# rotaryboard-small.net
KiCad netlist of a schematic drawn in EAGLE
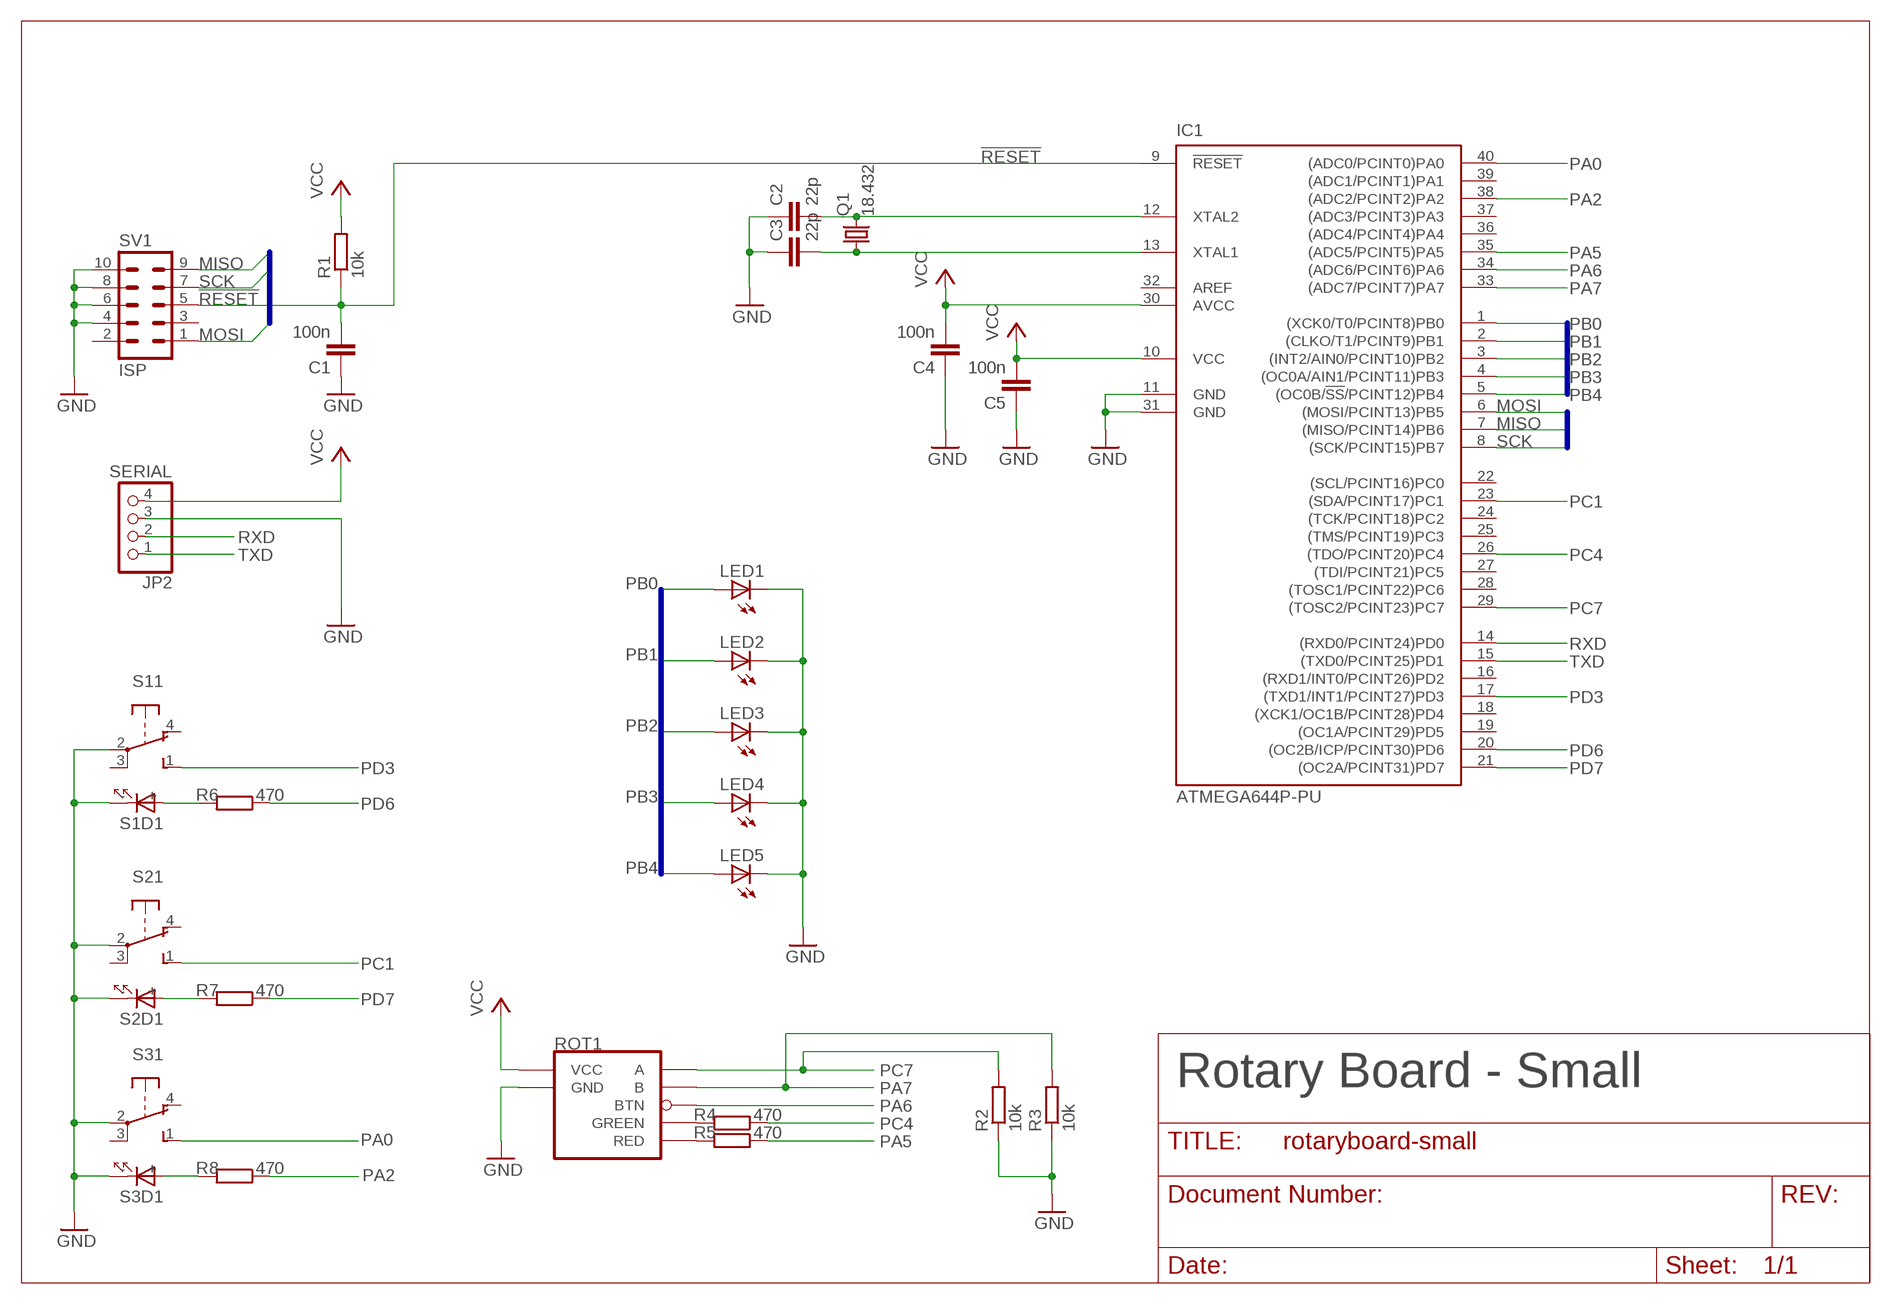
[diagram p0: schematic, sheet 1]

(export (version "E")
  (design (tool "Eeschema 10.0.6"))
  (components
    (comp (ref "C1")
      (value "100n")
      (footprint "eagle-import:C050-025X075")
      (libsource (lib "eagle-import") (part "C-EU050-025X075"))
    )
    (comp (ref "C2")
      (value "22p")
      (footprint "eagle-import:C050-025X075")
      (libsource (lib "eagle-import") (part "C-EU050-025X075"))
    )
    (comp (ref "C3")
      (value "22p")
      (footprint "eagle-import:C050-025X075")
      (libsource (lib "eagle-import") (part "C-EU050-025X075"))
    )
    (comp (ref "C4")
      (value "100n")
      (footprint "eagle-import:C050-025X075")
      (libsource (lib "eagle-import") (part "C-EU050-025X075"))
    )
    (comp (ref "C5")
      (value "100n")
      (footprint "eagle-import:C050-025X075")
      (libsource (lib "eagle-import") (part "C-EU050-025X075"))
    )
    (comp (ref "IC1")
      (value "ATMEGA644P-PU")
      (footprint "eagle-import:DIL40")
      (libsource (lib "eagle-import") (part "MEGA164P/324P/644P-PU"))
    )
    (comp (ref "JP2")
      (value "SERIAL")
      (footprint "eagle-import:1X04")
      (libsource (lib "eagle-import") (part "PINHD-1X4"))
    )
    (comp (ref "LED1")
      (value "LED3MM")
      (footprint "eagle-import:LED3MM")
      (libsource (lib "eagle-import") (part "LED3MM"))
    )
    (comp (ref "LED2")
      (value "LED3MM")
      (footprint "eagle-import:LED3MM")
      (libsource (lib "eagle-import") (part "LED3MM"))
    )
    (comp (ref "LED3")
      (value "LED3MM")
      (footprint "eagle-import:LED3MM")
      (libsource (lib "eagle-import") (part "LED3MM"))
    )
    (comp (ref "LED4")
      (value "LED3MM")
      (footprint "eagle-import:LED3MM")
      (libsource (lib "eagle-import") (part "LED3MM"))
    )
    (comp (ref "LED5")
      (value "LED3MM")
      (footprint "eagle-import:LED3MM")
      (libsource (lib "eagle-import") (part "LED3MM"))
    )
    (comp (ref "Q1")
      (value "18.432")
      (footprint "eagle-import:HC18U-V")
      (libsource (lib "eagle-import") (part "CRYSTALHC18U-V"))
    )
    (comp (ref "R1")
      (value "10k")
      (footprint "eagle-import:0207_10")
      (libsource (lib "eagle-import") (part "R-EU_0207/10"))
    )
    (comp (ref "R2")
      (value "10k")
      (footprint "eagle-import:0207_10")
      (libsource (lib "eagle-import") (part "R-EU_0207/10"))
    )
    (comp (ref "R3")
      (value "10k")
      (footprint "eagle-import:0207_10")
      (libsource (lib "eagle-import") (part "R-EU_0207/10"))
    )
    (comp (ref "R4")
      (value "470")
      (footprint "eagle-import:0207_10")
      (libsource (lib "eagle-import") (part "R-EU_0207/10"))
    )
    (comp (ref "R5")
      (value "470")
      (footprint "eagle-import:0207_10")
      (libsource (lib "eagle-import") (part "R-EU_0207/10"))
    )
    (comp (ref "R6")
      (value "470")
      (footprint "eagle-import:0207_10")
      (libsource (lib "eagle-import") (part "R-EU_0207/10"))
    )
    (comp (ref "R7")
      (value "470")
      (footprint "eagle-import:0207_10")
      (libsource (lib "eagle-import") (part "R-EU_0207/10"))
    )
    (comp (ref "R8")
      (value "470")
      (footprint "eagle-import:0207_10")
      (libsource (lib "eagle-import") (part "R-EU_0207/10"))
    )
    (comp (ref "ROT1")
      (value "DPL12SVCUSTOM")
      (footprint "eagle-import:DPL12SV")
      (libsource (lib "eagle-import") (part "DPL12SVCUSTOM"))
    )
    (comp (ref "S1")
      (value "SRKL")
      (footprint "eagle-import:SRKL")
      (libsource (lib "eagle-import") (part "SRKL"))
    )
    (comp (ref "S2")
      (value "SRKL")
      (footprint "eagle-import:SRKL")
      (libsource (lib "eagle-import") (part "SRKL"))
    )
    (comp (ref "S3")
      (value "SRKL")
      (footprint "eagle-import:SRKL")
      (libsource (lib "eagle-import") (part "SRKL"))
    )
    (comp (ref "SV1")
      (value "ISP")
      (footprint "eagle-import:ML10")
      (libsource (lib "eagle-import") (part "ML10"))
    )
  )
  (nets
    (net (code "6") (name "/AREF") (class "Default")
      (node (ref "IC1") (pin "32") (pinfunction "AREF_32") (pintype "power_in"))
    )
    (net (code "7") (name "/LEDS:PB[0..4]") (class "Default")
      (node (ref "IC1") (pin "5") (pinfunction "(OC0B/~{SS}/PCINT12)PB4_5") (pintype "bidirectional"))
      (node (ref "LED5") (pin "A") (pinfunction "A_A") (pintype "passive"))
    )
    (net (code "8") (name "/MISO") (class "Default")
      (node (ref "IC1") (pin "7") (pinfunction "(MISO/PCINT14)PB6_7") (pintype "bidirectional"))
      (node (ref "SV1") (pin "9") (pinfunction "9_9") (pintype "passive"))
    )
    (net (code "9") (name "/MOSI") (class "Default")
      (node (ref "IC1") (pin "6") (pinfunction "(MOSI/PCINT13)PB5_6") (pintype "bidirectional"))
      (node (ref "SV1") (pin "1") (pinfunction "1_1") (pintype "passive"))
    )
    (net (code "10") (name "/PA0") (class "Default")
      (node (ref "IC1") (pin "40") (pinfunction "(ADC0/PCINT0)PA0_40") (pintype "bidirectional"))
      (node (ref "S3") (pin "1") (pinfunction "S_1") (pintype "passive"))
    )
    (net (code "11") (name "/PA2") (class "Default")
      (node (ref "IC1") (pin "38") (pinfunction "(ADC2/PCINT2)PA2_38") (pintype "bidirectional"))
      (node (ref "R8") (pin "1") (pinfunction "1_1") (pintype "passive"))
    )
    (net (code "12") (name "/PA5") (class "Default")
      (node (ref "IC1") (pin "35") (pinfunction "(ADC5/PCINT5)PA5_35") (pintype "bidirectional"))
      (node (ref "R5") (pin "1") (pinfunction "1_1") (pintype "passive"))
    )
    (net (code "13") (name "/PA6") (class "Default")
      (node (ref "IC1") (pin "34") (pinfunction "(ADC6/PCINT6)PA6_34") (pintype "bidirectional"))
      (node (ref "ROT1") (pin "BTN") (pinfunction "BTN_BTN") (pintype "output"))
    )
    (net (code "14") (name "/PA7") (class "Default")
      (node (ref "IC1") (pin "33") (pinfunction "(ADC7/PCINT7)PA7_33") (pintype "bidirectional"))
      (node (ref "R3") (pin "2") (pinfunction "2_2") (pintype "passive"))
      (node (ref "ROT1") (pin "B") (pinfunction "B_B") (pintype "output"))
    )
    (net (code "15") (name "/PB0") (class "Default")
      (node (ref "IC1") (pin "1") (pinfunction "(XCK0/T0/PCINT8)PB0_1") (pintype "bidirectional"))
      (node (ref "LED1") (pin "A") (pinfunction "A_A") (pintype "passive"))
    )
    (net (code "16") (name "/PB1") (class "Default")
      (node (ref "IC1") (pin "2") (pinfunction "(CLKO/T1/PCINT9)PB1_2") (pintype "bidirectional"))
      (node (ref "LED2") (pin "A") (pinfunction "A_A") (pintype "passive"))
    )
    (net (code "17") (name "/PB2") (class "Default")
      (node (ref "IC1") (pin "3") (pinfunction "(INT2/AIN0/PCINT10)PB2_3") (pintype "bidirectional"))
      (node (ref "LED3") (pin "A") (pinfunction "A_A") (pintype "passive"))
    )
    (net (code "18") (name "/PB3") (class "Default")
      (node (ref "IC1") (pin "4") (pinfunction "(OC0A/AIN1/PCINT11)PB3_4") (pintype "bidirectional"))
      (node (ref "LED4") (pin "A") (pinfunction "A_A") (pintype "passive"))
    )
    (net (code "19") (name "/PC1") (class "Default")
      (node (ref "IC1") (pin "23") (pinfunction "(SDA/PCINT17)PC1_23") (pintype "bidirectional"))
      (node (ref "S2") (pin "1") (pinfunction "S_1") (pintype "passive"))
    )
    (net (code "20") (name "/PC4") (class "Default")
      (node (ref "IC1") (pin "26") (pinfunction "(TDO/PCINT20)PC4_26") (pintype "bidirectional"))
      (node (ref "R4") (pin "1") (pinfunction "1_1") (pintype "passive"))
    )
    (net (code "21") (name "/PC7") (class "Default")
      (node (ref "IC1") (pin "29") (pinfunction "(TOSC2/PCINT23)PC7_29") (pintype "bidirectional"))
      (node (ref "R2") (pin "2") (pinfunction "2_2") (pintype "passive"))
      (node (ref "ROT1") (pin "A") (pinfunction "A_A") (pintype "output"))
    )
    (net (code "22") (name "/PD3") (class "Default")
      (node (ref "IC1") (pin "17") (pinfunction "(TXD1/INT1/PCINT27)PD3_17") (pintype "bidirectional"))
      (node (ref "S1") (pin "1") (pinfunction "S_1") (pintype "passive"))
    )
    (net (code "23") (name "/PD6") (class "Default")
      (node (ref "IC1") (pin "20") (pinfunction "(OC2B/ICP/PCINT30)PD6_20") (pintype "bidirectional"))
      (node (ref "R6") (pin "1") (pinfunction "1_1") (pintype "passive"))
    )
    (net (code "24") (name "/PD7") (class "Default")
      (node (ref "IC1") (pin "21") (pinfunction "(OC2A/PCINT31)PD7_21") (pintype "bidirectional"))
      (node (ref "R7") (pin "1") (pinfunction "1_1") (pintype "passive"))
    )
    (net (code "25") (name "/RXD") (class "Default")
      (node (ref "IC1") (pin "14") (pinfunction "(RXD0/PCINT24)PD0_14") (pintype "bidirectional"))
      (node (ref "JP2") (pin "2") (pinfunction "2_2") (pintype "passive"))
    )
    (net (code "26") (name "/SCK") (class "Default")
      (node (ref "IC1") (pin "8") (pinfunction "(SCK/PCINT15)PB7_8") (pintype "bidirectional"))
      (node (ref "SV1") (pin "7") (pinfunction "7_7") (pintype "passive"))
    )
    (net (code "27") (name "/TXD") (class "Default")
      (node (ref "IC1") (pin "15") (pinfunction "(TXD0/PCINT25)PD1_15") (pintype "bidirectional"))
      (node (ref "JP2") (pin "1") (pinfunction "1_1") (pintype "passive"))
    )
    (net (code "28") (name "/~{RESET}") (class "Default")
      (node (ref "C1") (pin "2") (pinfunction "2_2") (pintype "passive"))
      (node (ref "IC1") (pin "9") (pinfunction "~{RESET}_9") (pintype "input"))
      (node (ref "R1") (pin "1") (pinfunction "1_1") (pintype "passive"))
      (node (ref "SV1") (pin "5") (pinfunction "5_5") (pintype "passive"))
    )
    (net (code "29") (name "GND") (class "Default")
      (node (ref "C1") (pin "1") (pinfunction "1_1") (pintype "passive"))
      (node (ref "C2") (pin "1") (pinfunction "1_1") (pintype "passive"))
      (node (ref "C3") (pin "1") (pinfunction "1_1") (pintype "passive"))
      (node (ref "C4") (pin "1") (pinfunction "1_1") (pintype "passive"))
      (node (ref "C5") (pin "1") (pinfunction "1_1") (pintype "passive"))
      (node (ref "IC1") (pin "11") (pinfunction "GND_11") (pintype "power_in"))
      (node (ref "IC1") (pin "31") (pinfunction "GND_31") (pintype "power_in"))
      (node (ref "JP2") (pin "3") (pinfunction "3_3") (pintype "passive"))
      (node (ref "LED1") (pin "K") (pinfunction "C_K") (pintype "passive"))
      (node (ref "LED2") (pin "K") (pinfunction "C_K") (pintype "passive"))
      (node (ref "LED3") (pin "K") (pinfunction "C_K") (pintype "passive"))
      (node (ref "LED4") (pin "K") (pinfunction "C_K") (pintype "passive"))
      (node (ref "LED5") (pin "K") (pinfunction "C_K") (pintype "passive"))
      (node (ref "R2") (pin "1") (pinfunction "1_1") (pintype "passive"))
      (node (ref "R3") (pin "1") (pinfunction "1_1") (pintype "passive"))
      (node (ref "ROT1") (pin "GND") (pinfunction "GND_GND") (pintype "power_in"))
      (node (ref "S1") (pin "-") (pinfunction "C_-") (pintype "passive"))
      (node (ref "S1") (pin "2") (pinfunction "P_2") (pintype "passive"))
      (node (ref "S2") (pin "-") (pinfunction "C_-") (pintype "passive"))
      (node (ref "S2") (pin "2") (pinfunction "P_2") (pintype "passive"))
      (node (ref "S3") (pin "-") (pinfunction "C_-") (pintype "passive"))
      (node (ref "S3") (pin "2") (pinfunction "P_2") (pintype "passive"))
      (node (ref "SV1") (pin "10") (pinfunction "10_10") (pintype "passive"))
      (node (ref "SV1") (pin "4") (pinfunction "4_4") (pintype "passive"))
      (node (ref "SV1") (pin "6") (pinfunction "6_6") (pintype "passive"))
      (node (ref "SV1") (pin "8") (pinfunction "8_8") (pintype "passive"))
    )
    (net (code "30") (name "Net-(IC1-XTAL1)") (class "Default")
      (node (ref "C3") (pin "2") (pinfunction "2_2") (pintype "passive"))
      (node (ref "IC1") (pin "13") (pinfunction "XTAL1_13") (pintype "input"))
      (node (ref "Q1") (pin "1") (pinfunction "1_1") (pintype "passive"))
    )
    (net (code "31") (name "Net-(IC1-XTAL2)") (class "Default")
      (node (ref "C2") (pin "2") (pinfunction "2_2") (pintype "passive"))
      (node (ref "IC1") (pin "12") (pinfunction "XTAL2_12") (pintype "output"))
      (node (ref "Q1") (pin "2") (pinfunction "2_2") (pintype "passive"))
    )
    (net (code "32") (name "Net-(R4-Pad2)") (class "Default")
      (node (ref "R4") (pin "2") (pinfunction "2_2") (pintype "passive"))
      (node (ref "ROT1") (pin "GREEN") (pinfunction "GREEN_GREEN") (pintype "passive"))
    )
    (net (code "33") (name "Net-(R5-Pad2)") (class "Default")
      (node (ref "R5") (pin "2") (pinfunction "2_2") (pintype "passive"))
      (node (ref "ROT1") (pin "RED") (pinfunction "RED_RED") (pintype "passive"))
    )
    (net (code "34") (name "Net-(S1B-A)") (class "Default")
      (node (ref "R6") (pin "2") (pinfunction "2_2") (pintype "passive"))
      (node (ref "S1") (pin "+") (pinfunction "A_+") (pintype "passive"))
    )
    (net (code "35") (name "Net-(S2B-A)") (class "Default")
      (node (ref "R7") (pin "2") (pinfunction "2_2") (pintype "passive"))
      (node (ref "S2") (pin "+") (pinfunction "A_+") (pintype "passive"))
    )
    (net (code "36") (name "Net-(S3B-A)") (class "Default")
      (node (ref "R8") (pin "2") (pinfunction "2_2") (pintype "passive"))
      (node (ref "S3") (pin "+") (pinfunction "A_+") (pintype "passive"))
    )
    (net (code "37") (name "VCC") (class "Default")
      (node (ref "C4") (pin "2") (pinfunction "2_2") (pintype "passive"))
      (node (ref "C5") (pin "2") (pinfunction "2_2") (pintype "passive"))
      (node (ref "IC1") (pin "10") (pinfunction "VCC_10") (pintype "power_in"))
      (node (ref "IC1") (pin "30") (pinfunction "AVCC_30") (pintype "power_in"))
      (node (ref "JP2") (pin "4") (pinfunction "4_4") (pintype "passive"))
      (node (ref "R1") (pin "2") (pinfunction "2_2") (pintype "passive"))
      (node (ref "ROT1") (pin "VCC") (pinfunction "VCC_VCC") (pintype "power_in"))
    )
    (net (code "38") (name "unconnected-(IC1-(ADC1{slash}PCINT1)PA1-Pad39)") (class "Default")
      (node (ref "IC1") (pin "39") (pinfunction "(ADC1/PCINT1)PA1_39") (pintype "bidirectional"))
    )
    (net (code "39") (name "unconnected-(IC1-(ADC3{slash}PCINT3)PA3-Pad37)") (class "Default")
      (node (ref "IC1") (pin "37") (pinfunction "(ADC3/PCINT3)PA3_37") (pintype "bidirectional"))
    )
    (net (code "40") (name "unconnected-(IC1-(ADC4{slash}PCINT4)PA4-Pad36)") (class "Default")
      (node (ref "IC1") (pin "36") (pinfunction "(ADC4/PCINT4)PA4_36") (pintype "bidirectional"))
    )
    (net (code "41") (name "unconnected-(IC1-(OC1A{slash}PCINT29)PD5-Pad19)") (class "Default")
      (node (ref "IC1") (pin "19") (pinfunction "(OC1A/PCINT29)PD5_19") (pintype "bidirectional"))
    )
    (net (code "42") (name "unconnected-(IC1-(RXD1{slash}INT0{slash}PCINT26)PD2-Pad16)") (class "Default")
      (node (ref "IC1") (pin "16") (pinfunction "(RXD1/INT0/PCINT26)PD2_16") (pintype "bidirectional"))
    )
    (net (code "43") (name "unconnected-(IC1-(SCL{slash}PCINT16)PC0-Pad22)") (class "Default")
      (node (ref "IC1") (pin "22") (pinfunction "(SCL/PCINT16)PC0_22") (pintype "bidirectional"))
    )
    (net (code "44") (name "unconnected-(IC1-(TCK{slash}PCINT18)PC2-Pad24)") (class "Default")
      (node (ref "IC1") (pin "24") (pinfunction "(TCK/PCINT18)PC2_24") (pintype "bidirectional"))
    )
    (net (code "45") (name "unconnected-(IC1-(TDI{slash}PCINT21)PC5-Pad27)") (class "Default")
      (node (ref "IC1") (pin "27") (pinfunction "(TDI/PCINT21)PC5_27") (pintype "bidirectional"))
    )
    (net (code "46") (name "unconnected-(IC1-(TMS{slash}PCINT19)PC3-Pad25)") (class "Default")
      (node (ref "IC1") (pin "25") (pinfunction "(TMS/PCINT19)PC3_25") (pintype "bidirectional"))
    )
    (net (code "47") (name "unconnected-(IC1-(TOSC1{slash}PCINT22)PC6-Pad28)") (class "Default")
      (node (ref "IC1") (pin "28") (pinfunction "(TOSC1/PCINT22)PC6_28") (pintype "bidirectional"))
    )
    (net (code "48") (name "unconnected-(IC1-(XCK1{slash}OC1B{slash}PCINT28)PD4-Pad18)") (class "Default")
      (node (ref "IC1") (pin "18") (pinfunction "(XCK1/OC1B/PCINT28)PD4_18") (pintype "bidirectional"))
    )
    (net (code "49") (name "unconnected-(S1A-O-Pad4)") (class "Default")
      (node (ref "S1") (pin "4") (pinfunction "O_4") (pintype "passive"))
    )
    (net (code "50") (name "unconnected-(S1A-P-Pad3)") (class "Default")
      (node (ref "S1") (pin "3") (pinfunction "P_3") (pintype "passive"))
    )
    (net (code "51") (name "unconnected-(S2A-O-Pad4)") (class "Default")
      (node (ref "S2") (pin "4") (pinfunction "O_4") (pintype "passive"))
    )
    (net (code "52") (name "unconnected-(S2A-P-Pad3)") (class "Default")
      (node (ref "S2") (pin "3") (pinfunction "P_3") (pintype "passive"))
    )
    (net (code "53") (name "unconnected-(S3A-O-Pad4)") (class "Default")
      (node (ref "S3") (pin "4") (pinfunction "O_4") (pintype "passive"))
    )
    (net (code "54") (name "unconnected-(S3A-P-Pad3)") (class "Default")
      (node (ref "S3") (pin "3") (pinfunction "P_3") (pintype "passive"))
    )
    (net (code "55") (name "unconnected-(SV1-Pad2)") (class "Default")
      (node (ref "SV1") (pin "2") (pinfunction "2_2") (pintype "passive"))
    )
    (net (code "56") (name "unconnected-(SV1-Pad3)") (class "Default")
      (node (ref "SV1") (pin "3") (pinfunction "3_3") (pintype "passive"))
    )
  )
)
